# Sheet1.net
KiCad netlist of a schematic drawn in Altium Designer
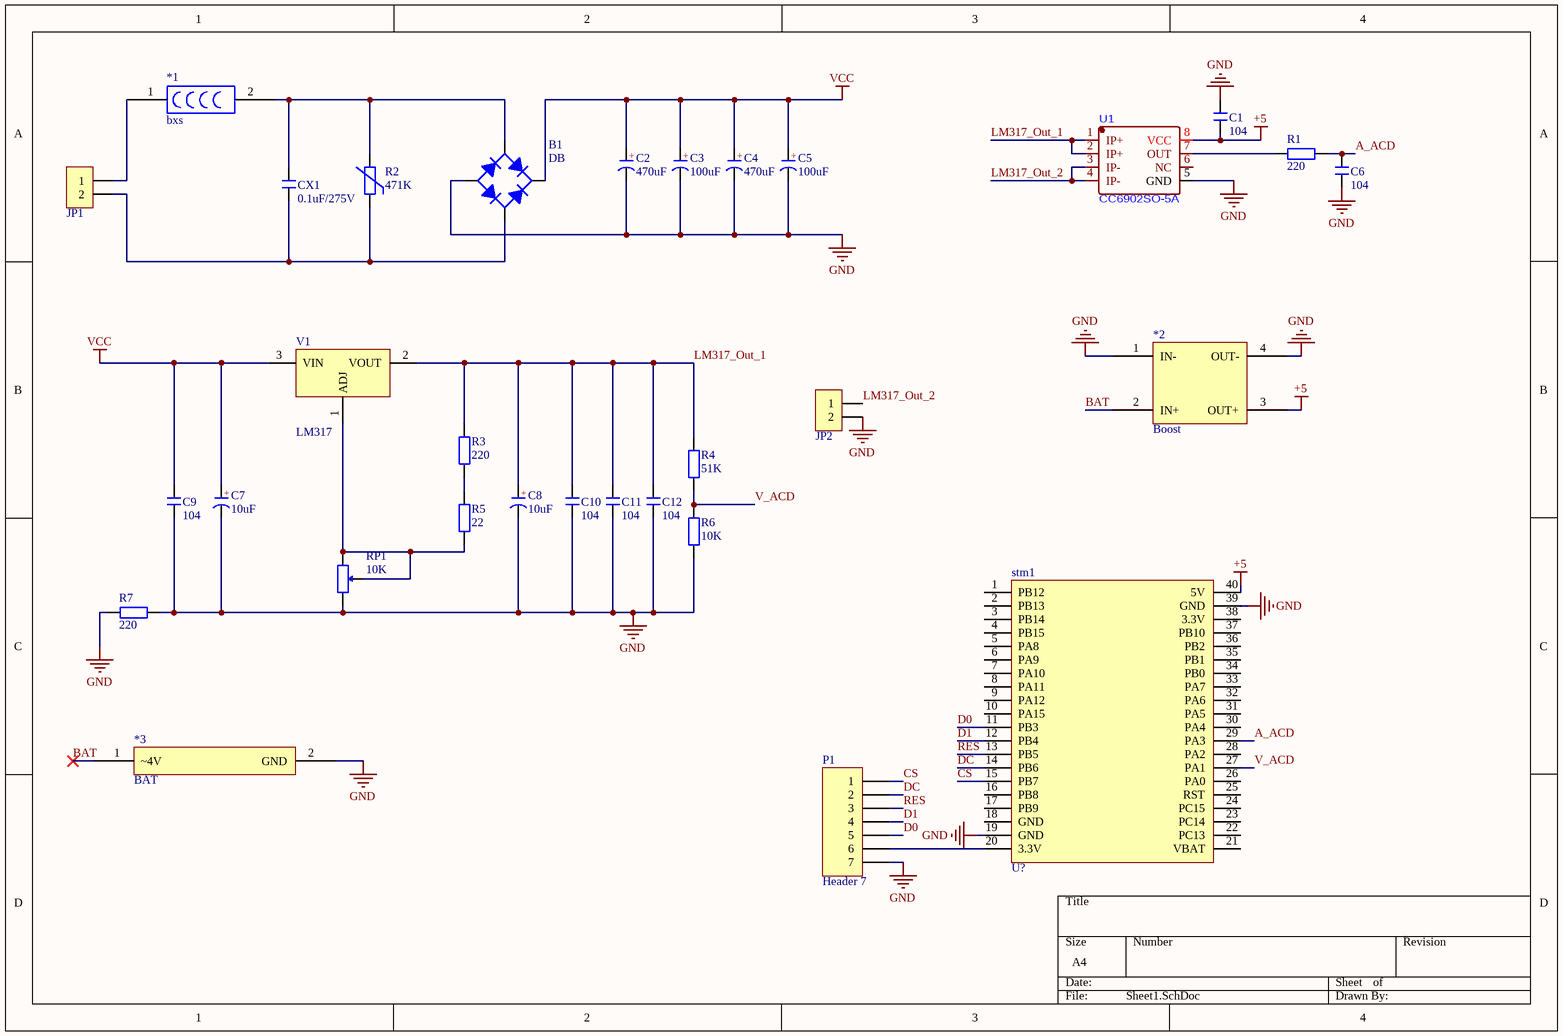
[diagram p0: Sheet1.SchDoc]

(export (version "E")
  (design (tool "Eeschema 10.0.6"))
  (components
    (comp (ref "*1") (value "bxs") (footprint "bxs") (libsource (lib "Schlib1") (part "bxs")))
    (comp (ref "*2") (value "Boost") (footprint "Boost") (libsource (lib "Schlib1") (part "Boost")))
    (comp (ref "*3") (value "BAT") (footprint "BAT") (libsource (lib "Schlib1") (part "BAT")))
    (comp (ref "B1")
      (value "DB")
      (footprint "GBU")
      (description "整流桥")
      (libsource (lib "02 - 二极管(LED)-三极管-整流桥") (part "DB"))
    )
    (comp (ref "C1")
      (value "104")
      (footprint "C 0805_M")
      (description "贴片电容")
      (libsource (lib "01 - 电容-电阻-电感") (part "C"))
    )
    (comp (ref "C2")
      (value "470uF")
      (footprint "CAP 3.5*8*11.5")
      (description "直插电解电容")
      (libsource (lib "01 - 电容-电阻-电感") (part "CE"))
    )
    (comp (ref "C3")
      (value "100uF")
      (footprint "CAP 3.5*8*11.5")
      (description "直插电解电容")
      (libsource (lib "01 - 电容-电阻-电感") (part "CE"))
    )
    (comp (ref "C4")
      (value "470uF")
      (footprint "CAP 3.5*8*11.5")
      (description "直插电解电容")
      (libsource (lib "01 - 电容-电阻-电感") (part "CE"))
    )
    (comp (ref "C5")
      (value "100uF")
      (footprint "CAP 3.5*8*11.5")
      (description "直插电解电容")
      (libsource (lib "01 - 电容-电阻-电感") (part "CE"))
    )
    (comp (ref "C6")
      (value "104")
      (footprint "C 0805_M")
      (description "贴片电容")
      (libsource (lib "01 - 电容-电阻-电感") (part "C"))
    )
    (comp (ref "C7")
      (value "10uF")
      (footprint "CAP 2.0*5*11")
      (description "直插电解电容")
      (libsource (lib "01 - 电容-电阻-电感") (part "CE"))
    )
    (comp (ref "C8")
      (value "10uF")
      (footprint "CAP 2.0*5*11")
      (description "直插电解电容")
      (libsource (lib "01 - 电容-电阻-电感") (part "CE"))
    )
    (comp (ref "C9")
      (value "104")
      (footprint "C 0805_M")
      (description "贴片电容")
      (libsource (lib "01 - 电容-电阻-电感") (part "C"))
    )
    (comp (ref "C10")
      (value "104")
      (footprint "C 0805_M")
      (description "贴片电容")
      (libsource (lib "01 - 电容-电阻-电感") (part "C"))
    )
    (comp (ref "C11")
      (value "104")
      (footprint "C 0805_M")
      (description "贴片电容")
      (libsource (lib "01 - 电容-电阻-电感") (part "C"))
    )
    (comp (ref "C12")
      (value "104")
      (footprint "C 0805_M")
      (description "贴片电容")
      (libsource (lib "01 - 电容-电阻-电感") (part "C"))
    )
    (comp (ref "CX1")
      (value "0.1uF/275V")
      (footprint "CX 10*13*11")
      (description "安规X电容")
      (libsource (lib "01 - 电容-电阻-电感") (part "CX"))
    )
    (comp (ref "JP1")
      (value "HDR-1X2")
      (footprint "KF2EDGK5.0-LI-2P")
      (description "2P接插件")
      (libsource (lib "21 - 接插件-脚距5.0mm") (part "Header 2"))
    )
    (comp (ref "JP2")
      (value "HDR-1X2")
      (footprint "KF2EDGK5.0-LI-2P")
      (description "2P接插件")
      (libsource (lib "21 - 接插件-脚距5.0mm") (part "Header 2"))
    )
    (comp (ref "P1")
      (value "Header 7")
      (footprint "HDR1X7")
      (description "Header, 7-Pin")
      (fields (field (name "PUBLISHER") "Altium Limited"))
      (libsource (lib "Miscellaneous Connectors") (part "Header 7"))
    )
    (comp (ref "R1")
      (value "220")
      (footprint "R 0805_M")
      (description "贴片电阻")
      (libsource (lib "01 - 电容-电阻-电感") (part "R"))
    )
    (comp (ref "R2")
      (value "471K")
      (footprint "VDR 9D-4.5")
      (description "压敏电阻")
      (libsource (lib "01 - 电容-电阻-电感") (part "R_VSR"))
    )
    (comp (ref "R3")
      (value "220")
      (footprint "R 0805_M")
      (description "贴片电阻")
      (libsource (lib "01 - 电容-电阻-电感") (part "R"))
    )
    (comp (ref "R4")
      (value "51K")
      (footprint "R 0805_M")
      (description "贴片电阻")
      (libsource (lib "01 - 电容-电阻-电感") (part "R"))
    )
    (comp (ref "R5")
      (value "22")
      (footprint "R 0805_M")
      (description "贴片电阻")
      (libsource (lib "01 - 电容-电阻-电感") (part "R"))
    )
    (comp (ref "R6")
      (value "10K")
      (footprint "R 0805_M")
      (description "贴片电阻")
      (libsource (lib "01 - 电容-电阻-电感") (part "R"))
    )
    (comp (ref "R7")
      (value "220")
      (footprint "R 0805_M")
      (description "贴片电阻")
      (libsource (lib "01 - 电容-电阻-电感") (part "R"))
    )
    (comp (ref "RP1")
      (value "10K")
      (footprint "3296W")
      (description "单联电位器")
      (libsource (lib "01 - 电容-电阻-电感") (part "RP"))
    )
    (comp (ref "stm1")
      (value "U?")
      (footprint "stm32f4x1cxu6_core")
      (libsource (lib "stm32f4x1cxu6") (part "stm32f4x1cxu6_core"))
    )
    (comp (ref "U1")
      (value "CC6902SO-5A")
      (footprint "SOP-8_L4.9-W3.9-P1.27-LS6.0-BL")
      (libsource (lib "CC6902SO-5A_2022-06-12") (part "CC6902SO-5A"))
    )
    (comp (ref "V1")
      (value "LM317")
      (footprint "TO220A")
      (description "可调线性稳压芯片")
      (libsource (lib "08 - 稳压芯片-电源管理芯片") (part "LM317"))
    )
  )
  (nets
    (net (code "1") (name "+5") (class "Default")
      (node (ref "*2") (pin "3") (pinfunction "OUT+_3") (pintype "passive"))
      (node (ref "C1") (pin "2") (pinfunction "2_2") (pintype "passive"))
      (node (ref "U1") (pin "8") (pinfunction "VCC_8") (pintype "passive"))
      (node (ref "stm1") (pin "40") (pinfunction "5V_40") (pintype "passive"))
    )
    (net (code "2") (name "/A_ACD") (class "Default")
      (node (ref "C6") (pin "1") (pinfunction "1_1") (pintype "passive"))
      (node (ref "R1") (pin "1") (pinfunction "1_1") (pintype "passive"))
      (node (ref "stm1") (pin "29") (pinfunction "PA3_29") (pintype "passive"))
    )
    (net (code "3") (name "/BAT") (class "Default")
      (node (ref "*2") (pin "2") (pinfunction "IN+_2") (pintype "passive"))
      (node (ref "*3") (pin "1") (pinfunction "~4V_1") (pintype "passive"))
    )
    (net (code "4") (name "/CS") (class "Default")
      (node (ref "P1") (pin "1") (pinfunction "1_1") (pintype "passive"))
      (node (ref "stm1") (pin "15") (pinfunction "PB7_15") (pintype "passive"))
    )
    (net (code "5") (name "/D0") (class "Default")
      (node (ref "P1") (pin "5") (pinfunction "5_5") (pintype "passive"))
      (node (ref "stm1") (pin "11") (pinfunction "PB3_11") (pintype "passive"))
    )
    (net (code "6") (name "/D1") (class "Default")
      (node (ref "P1") (pin "4") (pinfunction "4_4") (pintype "passive"))
      (node (ref "stm1") (pin "12") (pinfunction "PB4_12") (pintype "passive"))
    )
    (net (code "7") (name "/DC") (class "Default")
      (node (ref "P1") (pin "2") (pinfunction "2_2") (pintype "passive"))
      (node (ref "stm1") (pin "14") (pinfunction "PB6_14") (pintype "passive"))
    )
    (net (code "8") (name "/LM317_Out_1") (class "Default")
      (node (ref "C10") (pin "2") (pinfunction "2_2") (pintype "passive"))
      (node (ref "C11") (pin "2") (pinfunction "2_2") (pintype "passive"))
      (node (ref "C12") (pin "2") (pinfunction "2_2") (pintype "passive"))
      (node (ref "C8") (pin "1") (pinfunction "A_1") (pintype "passive"))
      (node (ref "R3") (pin "2") (pinfunction "2_2") (pintype "passive"))
      (node (ref "R4") (pin "2") (pinfunction "2_2") (pintype "passive"))
      (node (ref "U1") (pin "1") (pinfunction "IP+_1") (pintype "passive"))
      (node (ref "U1") (pin "2") (pinfunction "IP+_2") (pintype "passive"))
      (node (ref "V1") (pin "2") (pinfunction "VOUT_2") (pintype "passive"))
    )
    (net (code "9") (name "/LM317_Out_2") (class "Default")
      (node (ref "JP2") (pin "1") (pinfunction "1_1") (pintype "passive"))
      (node (ref "U1") (pin "3") (pinfunction "IP-_3") (pintype "passive"))
      (node (ref "U1") (pin "4") (pinfunction "IP-_4") (pintype "passive"))
    )
    (net (code "10") (name "/RES") (class "Default")
      (node (ref "P1") (pin "3") (pinfunction "3_3") (pintype "passive"))
      (node (ref "stm1") (pin "13") (pinfunction "PB5_13") (pintype "passive"))
    )
    (net (code "11") (name "/V_ACD") (class "Default")
      (node (ref "R4") (pin "1") (pinfunction "1_1") (pintype "passive"))
      (node (ref "R6") (pin "2") (pinfunction "2_2") (pintype "passive"))
      (node (ref "stm1") (pin "27") (pinfunction "PA1_27") (pintype "passive"))
    )
    (net (code "12") (name "GND") (class "Default")
      (node (ref "*2") (pin "1") (pinfunction "IN-_1") (pintype "passive"))
      (node (ref "*2") (pin "4") (pinfunction "OUT-_4") (pintype "passive"))
      (node (ref "*3") (pin "2") (pinfunction "GND_2") (pintype "passive"))
      (node (ref "B1") (pin "DC-") (pinfunction "DC-_DC-") (pintype "passive"))
      (node (ref "C1") (pin "1") (pinfunction "1_1") (pintype "passive"))
      (node (ref "C10") (pin "1") (pinfunction "1_1") (pintype "passive"))
      (node (ref "C11") (pin "1") (pinfunction "1_1") (pintype "passive"))
      (node (ref "C12") (pin "1") (pinfunction "1_1") (pintype "passive"))
      (node (ref "C2") (pin "2") (pinfunction "K_2") (pintype "passive"))
      (node (ref "C3") (pin "2") (pinfunction "K_2") (pintype "passive"))
      (node (ref "C4") (pin "2") (pinfunction "K_2") (pintype "passive"))
      (node (ref "C5") (pin "2") (pinfunction "K_2") (pintype "passive"))
      (node (ref "C6") (pin "2") (pinfunction "2_2") (pintype "passive"))
      (node (ref "C7") (pin "2") (pinfunction "K_2") (pintype "passive"))
      (node (ref "C8") (pin "2") (pinfunction "K_2") (pintype "passive"))
      (node (ref "C9") (pin "1") (pinfunction "1_1") (pintype "passive"))
      (node (ref "JP2") (pin "2") (pinfunction "2_2") (pintype "passive"))
      (node (ref "P1") (pin "7") (pinfunction "7_7") (pintype "passive"))
      (node (ref "R6") (pin "1") (pinfunction "1_1") (pintype "passive"))
      (node (ref "R7") (pin "1") (pinfunction "1_1") (pintype "passive"))
      (node (ref "R7") (pin "2") (pinfunction "2_2") (pintype "passive"))
      (node (ref "RP1") (pin "3") (pinfunction "3_3") (pintype "passive"))
      (node (ref "U1") (pin "5") (pinfunction "GND_5") (pintype "passive"))
      (node (ref "stm1") (pin "19") (pinfunction "GND_19") (pintype "passive"))
      (node (ref "stm1") (pin "39") (pinfunction "GND_39") (pintype "passive"))
    )
    (net (code "13") (name "Net-(*1-Pad1)") (class "Default")
      (node (ref "*1") (pin "1") (pinfunction "1_1") (pintype "passive"))
      (node (ref "JP1") (pin "1") (pinfunction "1_1") (pintype "passive"))
    )
    (net (code "14") (name "Net-(*1-Pad2)") (class "Default")
      (node (ref "*1") (pin "2") (pinfunction "2_2") (pintype "passive"))
      (node (ref "B1") (pin "AC1") (pinfunction "AC1_AC1") (pintype "passive"))
      (node (ref "CX1") (pin "2") (pinfunction "2_2") (pintype "passive"))
      (node (ref "R2") (pin "2") (pinfunction "2_2") (pintype "passive"))
    )
    (net (code "15") (name "Net-(B1-PadAC2)") (class "Default")
      (node (ref "B1") (pin "AC2") (pinfunction "AC2_AC2") (pintype "passive"))
      (node (ref "CX1") (pin "1") (pinfunction "1_1") (pintype "passive"))
      (node (ref "JP1") (pin "2") (pinfunction "2_2") (pintype "passive"))
      (node (ref "R2") (pin "1") (pinfunction "1_1") (pintype "passive"))
    )
    (net (code "16") (name "Net-(P1-Pad6)") (class "Default")
      (node (ref "P1") (pin "6") (pinfunction "6_6") (pintype "passive"))
      (node (ref "stm1") (pin "20") (pinfunction "3.3V_20") (pintype "passive"))
    )
    (net (code "17") (name "Net-(R3-Pad1)") (class "Default")
      (node (ref "R3") (pin "1") (pinfunction "1_1") (pintype "passive"))
      (node (ref "R5") (pin "2") (pinfunction "2_2") (pintype "passive"))
    )
    (net (code "18") (name "Net-(U1-OUT)") (class "Default")
      (node (ref "R1") (pin "2") (pinfunction "2_2") (pintype "passive"))
      (node (ref "U1") (pin "7") (pinfunction "OUT_7") (pintype "passive"))
    )
    (net (code "19") (name "Net-(V1-ADJ)") (class "Default")
      (node (ref "R5") (pin "1") (pinfunction "1_1") (pintype "passive"))
      (node (ref "RP1") (pin "1") (pinfunction "1_1") (pintype "passive"))
      (node (ref "RP1") (pin "2") (pinfunction "2_2") (pintype "passive"))
      (node (ref "V1") (pin "1") (pinfunction "ADJ_1") (pintype "passive"))
    )
    (net (code "20") (name "VCC") (class "Default")
      (node (ref "B1") (pin "DC+") (pinfunction "DC+_DC+") (pintype "passive"))
      (node (ref "C2") (pin "1") (pinfunction "A_1") (pintype "passive"))
      (node (ref "C3") (pin "1") (pinfunction "A_1") (pintype "passive"))
      (node (ref "C4") (pin "1") (pinfunction "A_1") (pintype "passive"))
      (node (ref "C5") (pin "1") (pinfunction "A_1") (pintype "passive"))
      (node (ref "C7") (pin "1") (pinfunction "A_1") (pintype "passive"))
      (node (ref "C9") (pin "2") (pinfunction "2_2") (pintype "passive"))
      (node (ref "V1") (pin "3") (pinfunction "VIN_3") (pintype "passive"))
    )
    (net (code "21") (name "unconnected-(U1-NC-Pad6)") (class "Default")
      (node (ref "U1") (pin "6") (pinfunction "NC_6") (pintype "passive"))
    )
    (net (code "22") (name "unconnected-(stm1-3.3V-Pad38)") (class "Default")
      (node (ref "stm1") (pin "38") (pinfunction "3.3V_38") (pintype "passive"))
    )
    (net (code "23") (name "unconnected-(stm1-GND-Pad18)") (class "Default")
      (node (ref "stm1") (pin "18") (pinfunction "GND_18") (pintype "passive"))
    )
    (net (code "24") (name "unconnected-(stm1-PA0-Pad26)") (class "Default")
      (node (ref "stm1") (pin "26") (pinfunction "PA0_26") (pintype "passive"))
    )
    (net (code "25") (name "unconnected-(stm1-PA2-Pad28)") (class "Default")
      (node (ref "stm1") (pin "28") (pinfunction "PA2_28") (pintype "passive"))
    )
    (net (code "26") (name "unconnected-(stm1-PA4-Pad30)") (class "Default")
      (node (ref "stm1") (pin "30") (pinfunction "PA4_30") (pintype "passive"))
    )
    (net (code "27") (name "unconnected-(stm1-PA5-Pad31)") (class "Default")
      (node (ref "stm1") (pin "31") (pinfunction "PA5_31") (pintype "passive"))
    )
    (net (code "28") (name "unconnected-(stm1-PA6-Pad32)") (class "Default")
      (node (ref "stm1") (pin "32") (pinfunction "PA6_32") (pintype "passive"))
    )
    (net (code "29") (name "unconnected-(stm1-PA7-Pad33)") (class "Default")
      (node (ref "stm1") (pin "33") (pinfunction "PA7_33") (pintype "passive"))
    )
    (net (code "30") (name "unconnected-(stm1-PA8-Pad5)") (class "Default")
      (node (ref "stm1") (pin "5") (pinfunction "PA8_5") (pintype "passive"))
    )
    (net (code "31") (name "unconnected-(stm1-PA9-Pad6)") (class "Default")
      (node (ref "stm1") (pin "6") (pinfunction "PA9_6") (pintype "passive"))
    )
    (net (code "32") (name "unconnected-(stm1-PA10-Pad7)") (class "Default")
      (node (ref "stm1") (pin "7") (pinfunction "PA10_7") (pintype "passive"))
    )
    (net (code "33") (name "unconnected-(stm1-PA11-Pad8)") (class "Default")
      (node (ref "stm1") (pin "8") (pinfunction "PA11_8") (pintype "passive"))
    )
    (net (code "34") (name "unconnected-(stm1-PA12-Pad9)") (class "Default")
      (node (ref "stm1") (pin "9") (pinfunction "PA12_9") (pintype "passive"))
    )
    (net (code "35") (name "unconnected-(stm1-PA15-Pad10)") (class "Default")
      (node (ref "stm1") (pin "10") (pinfunction "PA15_10") (pintype "passive"))
    )
    (net (code "36") (name "unconnected-(stm1-PB0-Pad34)") (class "Default")
      (node (ref "stm1") (pin "34") (pinfunction "PB0_34") (pintype "passive"))
    )
    (net (code "37") (name "unconnected-(stm1-PB1-Pad35)") (class "Default")
      (node (ref "stm1") (pin "35") (pinfunction "PB1_35") (pintype "passive"))
    )
    (net (code "38") (name "unconnected-(stm1-PB2-Pad36)") (class "Default")
      (node (ref "stm1") (pin "36") (pinfunction "PB2_36") (pintype "passive"))
    )
    (net (code "39") (name "unconnected-(stm1-PB8-Pad16)") (class "Default")
      (node (ref "stm1") (pin "16") (pinfunction "PB8_16") (pintype "passive"))
    )
    (net (code "40") (name "unconnected-(stm1-PB9-Pad17)") (class "Default")
      (node (ref "stm1") (pin "17") (pinfunction "PB9_17") (pintype "passive"))
    )
    (net (code "41") (name "unconnected-(stm1-PB10-Pad37)") (class "Default")
      (node (ref "stm1") (pin "37") (pinfunction "PB10_37") (pintype "passive"))
    )
    (net (code "42") (name "unconnected-(stm1-PB12-Pad1)") (class "Default")
      (node (ref "stm1") (pin "1") (pinfunction "PB12_1") (pintype "passive"))
    )
    (net (code "43") (name "unconnected-(stm1-PB13-Pad2)") (class "Default")
      (node (ref "stm1") (pin "2") (pinfunction "PB13_2") (pintype "passive"))
    )
    (net (code "44") (name "unconnected-(stm1-PB14-Pad3)") (class "Default")
      (node (ref "stm1") (pin "3") (pinfunction "PB14_3") (pintype "passive"))
    )
    (net (code "45") (name "unconnected-(stm1-PB15-Pad4)") (class "Default")
      (node (ref "stm1") (pin "4") (pinfunction "PB15_4") (pintype "passive"))
    )
    (net (code "46") (name "unconnected-(stm1-PC13-Pad22)") (class "Default")
      (node (ref "stm1") (pin "22") (pinfunction "PC13_22") (pintype "passive"))
    )
    (net (code "47") (name "unconnected-(stm1-PC14-Pad23)") (class "Default")
      (node (ref "stm1") (pin "23") (pinfunction "PC14_23") (pintype "passive"))
    )
    (net (code "48") (name "unconnected-(stm1-PC15-Pad24)") (class "Default")
      (node (ref "stm1") (pin "24") (pinfunction "PC15_24") (pintype "passive"))
    )
    (net (code "49") (name "unconnected-(stm1-RST-Pad25)") (class "Default")
      (node (ref "stm1") (pin "25") (pinfunction "RST_25") (pintype "passive"))
    )
    (net (code "50") (name "unconnected-(stm1-VBAT-Pad21)") (class "Default")
      (node (ref "stm1") (pin "21") (pinfunction "VBAT_21") (pintype "passive"))
    )
  )
)
